# barcode_scanner.net
KiCad netlist of a schematic drawn in Altium Designer
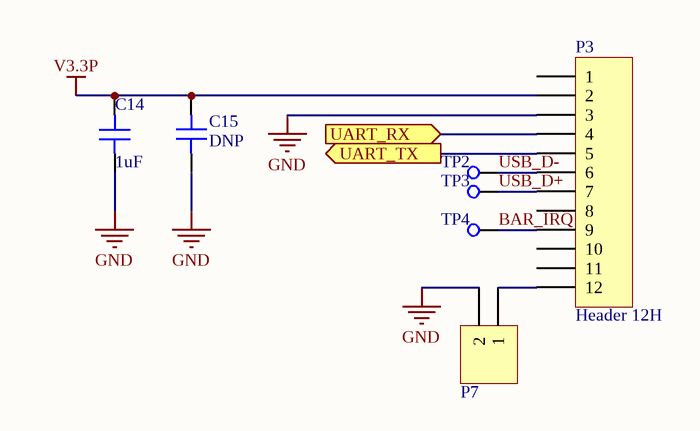
[diagram p0: barcode_scanner.SchDoc]

(export (version "E")
  (design (tool "Eeschema 10.0.6"))
  (components
    (comp (ref "C14")
      (value "1uF")
      (footprint "CAP 0603_1608")
      (description "SMT Capacitor")
      (fields (field (name "MF") "Murata") (field (name "MP") "GRT188R61H105KE13D"))
      (libsource (lib "Capacitor") (part "Capacitor"))
    )
    (comp (ref "C15")
      (value "DNP")
      (footprint "CAP 0603_1608")
      (description "SMT Capacitor")
      (libsource (lib "Capacitor") (part "Capacitor"))
    )
    (comp (ref "P3")
      (value "Header 12H")
      (footprint "Amphenol_FFC/FPC_12_0.5mm")
      (description "Header, 12-Pin, Right Angle")
      (fields
        (field (name "MF") "Amphenol")
        (field (name "MP") "10051922-1210ELF")
        (field (name "PUBLISHER") "Altium Limited")
      )
      (libsource (lib "Connector") (part "Header 12H"))
    )
    (comp (ref "P7")
      (value "DNP")
      (footprint "HDR1X2")
      (description "Header, 2-Pin")
      (fields (field (name "PUBLISHER") "Altium Limited"))
      (libsource (lib "Connector") (part "Header 2"))
    )
    (comp (ref "TP2")
      (value "Test Point")
      (footprint "TPSMD_S1")
      (libsource (lib "Passive") (part "Test Point"))
    )
    (comp (ref "TP3")
      (value "Test Point")
      (footprint "TPSMD_S1")
      (libsource (lib "Passive") (part "Test Point"))
    )
    (comp (ref "TP4")
      (value "Test Point")
      (footprint "TPSMD_S1")
      (libsource (lib "Passive") (part "Test Point"))
    )
  )
  (nets
    (net (code "1") (name "/BAR_IRQ") (class "Default")
      (node (ref "P3") (pin "9") (pinfunction "9_9") (pintype "passive"))
      (node (ref "TP4") (pin "1") (pinfunction "TP_1") (pintype "passive"))
    )
    (net (code "2") (name "/UART_RX") (class "Default")
      (node (ref "P3") (pin "4") (pinfunction "4_4") (pintype "passive"))
    )
    (net (code "3") (name "/UART_TX") (class "Default")
      (node (ref "P3") (pin "5") (pinfunction "5_5") (pintype "passive"))
    )
    (net (code "4") (name "/USB_D+") (class "Default")
      (node (ref "P3") (pin "7") (pinfunction "7_7") (pintype "passive"))
      (node (ref "TP3") (pin "1") (pinfunction "TP_1") (pintype "passive"))
    )
    (net (code "5") (name "/USB_D-") (class "Default")
      (node (ref "P3") (pin "6") (pinfunction "6_6") (pintype "passive"))
      (node (ref "TP2") (pin "1") (pinfunction "TP_1") (pintype "passive"))
    )
    (net (code "6") (name "GND") (class "Default")
      (node (ref "C14") (pin "1") (pinfunction "1_1") (pintype "passive"))
      (node (ref "C15") (pin "2") (pinfunction "2_2") (pintype "passive"))
      (node (ref "P3") (pin "3") (pinfunction "3_3") (pintype "passive"))
      (node (ref "P7") (pin "2") (pinfunction "2_2") (pintype "passive"))
    )
    (net (code "7") (name "Net-(P3-Pad12)") (class "Default")
      (node (ref "P3") (pin "12") (pinfunction "12_12") (pintype "passive"))
      (node (ref "P7") (pin "1") (pinfunction "1_1") (pintype "passive"))
    )
    (net (code "8") (name "V3.3P") (class "Default")
      (node (ref "C14") (pin "2") (pinfunction "2_2") (pintype "passive"))
      (node (ref "C15") (pin "1") (pinfunction "1_1") (pintype "passive"))
      (node (ref "P3") (pin "2") (pinfunction "2_2") (pintype "passive"))
    )
    (net (code "9") (name "unconnected-(P3-Pad1)") (class "Default")
      (node (ref "P3") (pin "1") (pinfunction "1_1") (pintype "passive"))
    )
    (net (code "10") (name "unconnected-(P3-Pad8)") (class "Default")
      (node (ref "P3") (pin "8") (pinfunction "8_8") (pintype "passive"))
    )
    (net (code "11") (name "unconnected-(P3-Pad10)") (class "Default")
      (node (ref "P3") (pin "10") (pinfunction "10_10") (pintype "passive"))
    )
    (net (code "12") (name "unconnected-(P3-Pad11)") (class "Default")
      (node (ref "P3") (pin "11") (pinfunction "11_11") (pintype "passive"))
    )
  )
)
